# Direction_Pad_SCHEMATIC.net
KiCad netlist of a schematic drawn in Altium Designer
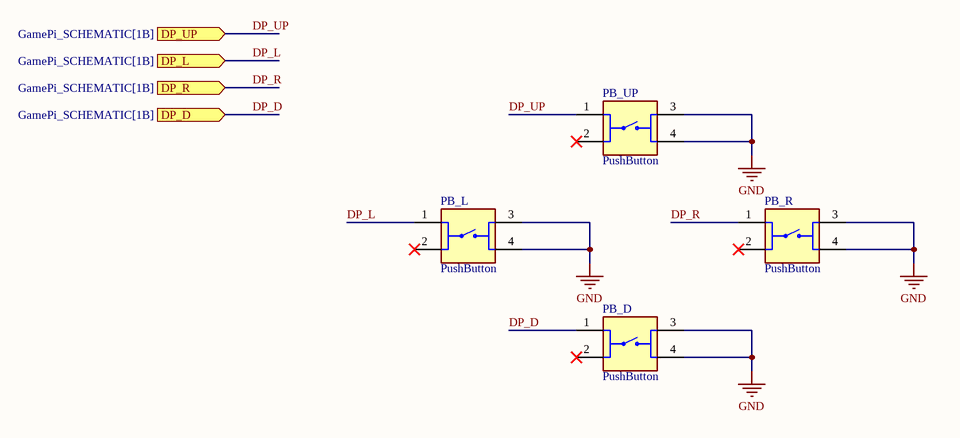
[diagram p0: Direction Pad_SCHEMATIC.SchDoc]

(export (version "E")
  (design (tool "Eeschema 10.0.6"))
  (components
    (comp (ref "PB_D")
      (value "PushButton")
      (footprint "Push Button")
      (libsource (lib "GamePi SCH LIB") (part "PushButton"))
    )
    (comp (ref "PB_L")
      (value "PushButton")
      (footprint "Push Button")
      (libsource (lib "GamePi SCH LIB") (part "PushButton"))
    )
    (comp (ref "PB_R")
      (value "PushButton")
      (footprint "Push Button")
      (libsource (lib "GamePi SCH LIB") (part "PushButton"))
    )
    (comp (ref "PB_UP")
      (value "PushButton")
      (footprint "Push Button")
      (libsource (lib "GamePi SCH LIB") (part "PushButton"))
    )
  )
  (nets
    (net (code "1") (name "/DP_D") (class "Default")
      (node (ref "PB_D") (pin "1") (pinfunction "1_1") (pintype "passive"))
    )
    (net (code "2") (name "/DP_L") (class "Default")
      (node (ref "PB_L") (pin "1") (pinfunction "1_1") (pintype "passive"))
    )
    (net (code "3") (name "/DP_R") (class "Default")
      (node (ref "PB_R") (pin "1") (pinfunction "1_1") (pintype "passive"))
    )
    (net (code "4") (name "/DP_UP") (class "Default")
      (node (ref "PB_UP") (pin "1") (pinfunction "1_1") (pintype "passive"))
    )
    (net (code "5") (name "GND") (class "Default")
      (node (ref "PB_D") (pin "3") (pinfunction "3_3") (pintype "passive"))
      (node (ref "PB_D") (pin "4") (pinfunction "4_4") (pintype "passive"))
      (node (ref "PB_L") (pin "3") (pinfunction "3_3") (pintype "passive"))
      (node (ref "PB_L") (pin "4") (pinfunction "4_4") (pintype "passive"))
      (node (ref "PB_R") (pin "3") (pinfunction "3_3") (pintype "passive"))
      (node (ref "PB_R") (pin "4") (pinfunction "4_4") (pintype "passive"))
      (node (ref "PB_UP") (pin "3") (pinfunction "3_3") (pintype "passive"))
      (node (ref "PB_UP") (pin "4") (pinfunction "4_4") (pintype "passive"))
    )
    (net (code "6") (name "unconnected-(PB_D-Pad2)") (class "Default")
      (node (ref "PB_D") (pin "2") (pinfunction "2_2") (pintype "passive+no_connect"))
    )
    (net (code "7") (name "unconnected-(PB_L-Pad2)") (class "Default")
      (node (ref "PB_L") (pin "2") (pinfunction "2_2") (pintype "passive+no_connect"))
    )
    (net (code "8") (name "unconnected-(PB_R-Pad2)") (class "Default")
      (node (ref "PB_R") (pin "2") (pinfunction "2_2") (pintype "passive+no_connect"))
    )
    (net (code "9") (name "unconnected-(PB_UP-Pad2)") (class "Default")
      (node (ref "PB_UP") (pin "2") (pinfunction "2_2") (pintype "passive+no_connect"))
    )
  )
)
